# Sch_Form.net
KiCad netlist of a schematic drawn in Altium Designer
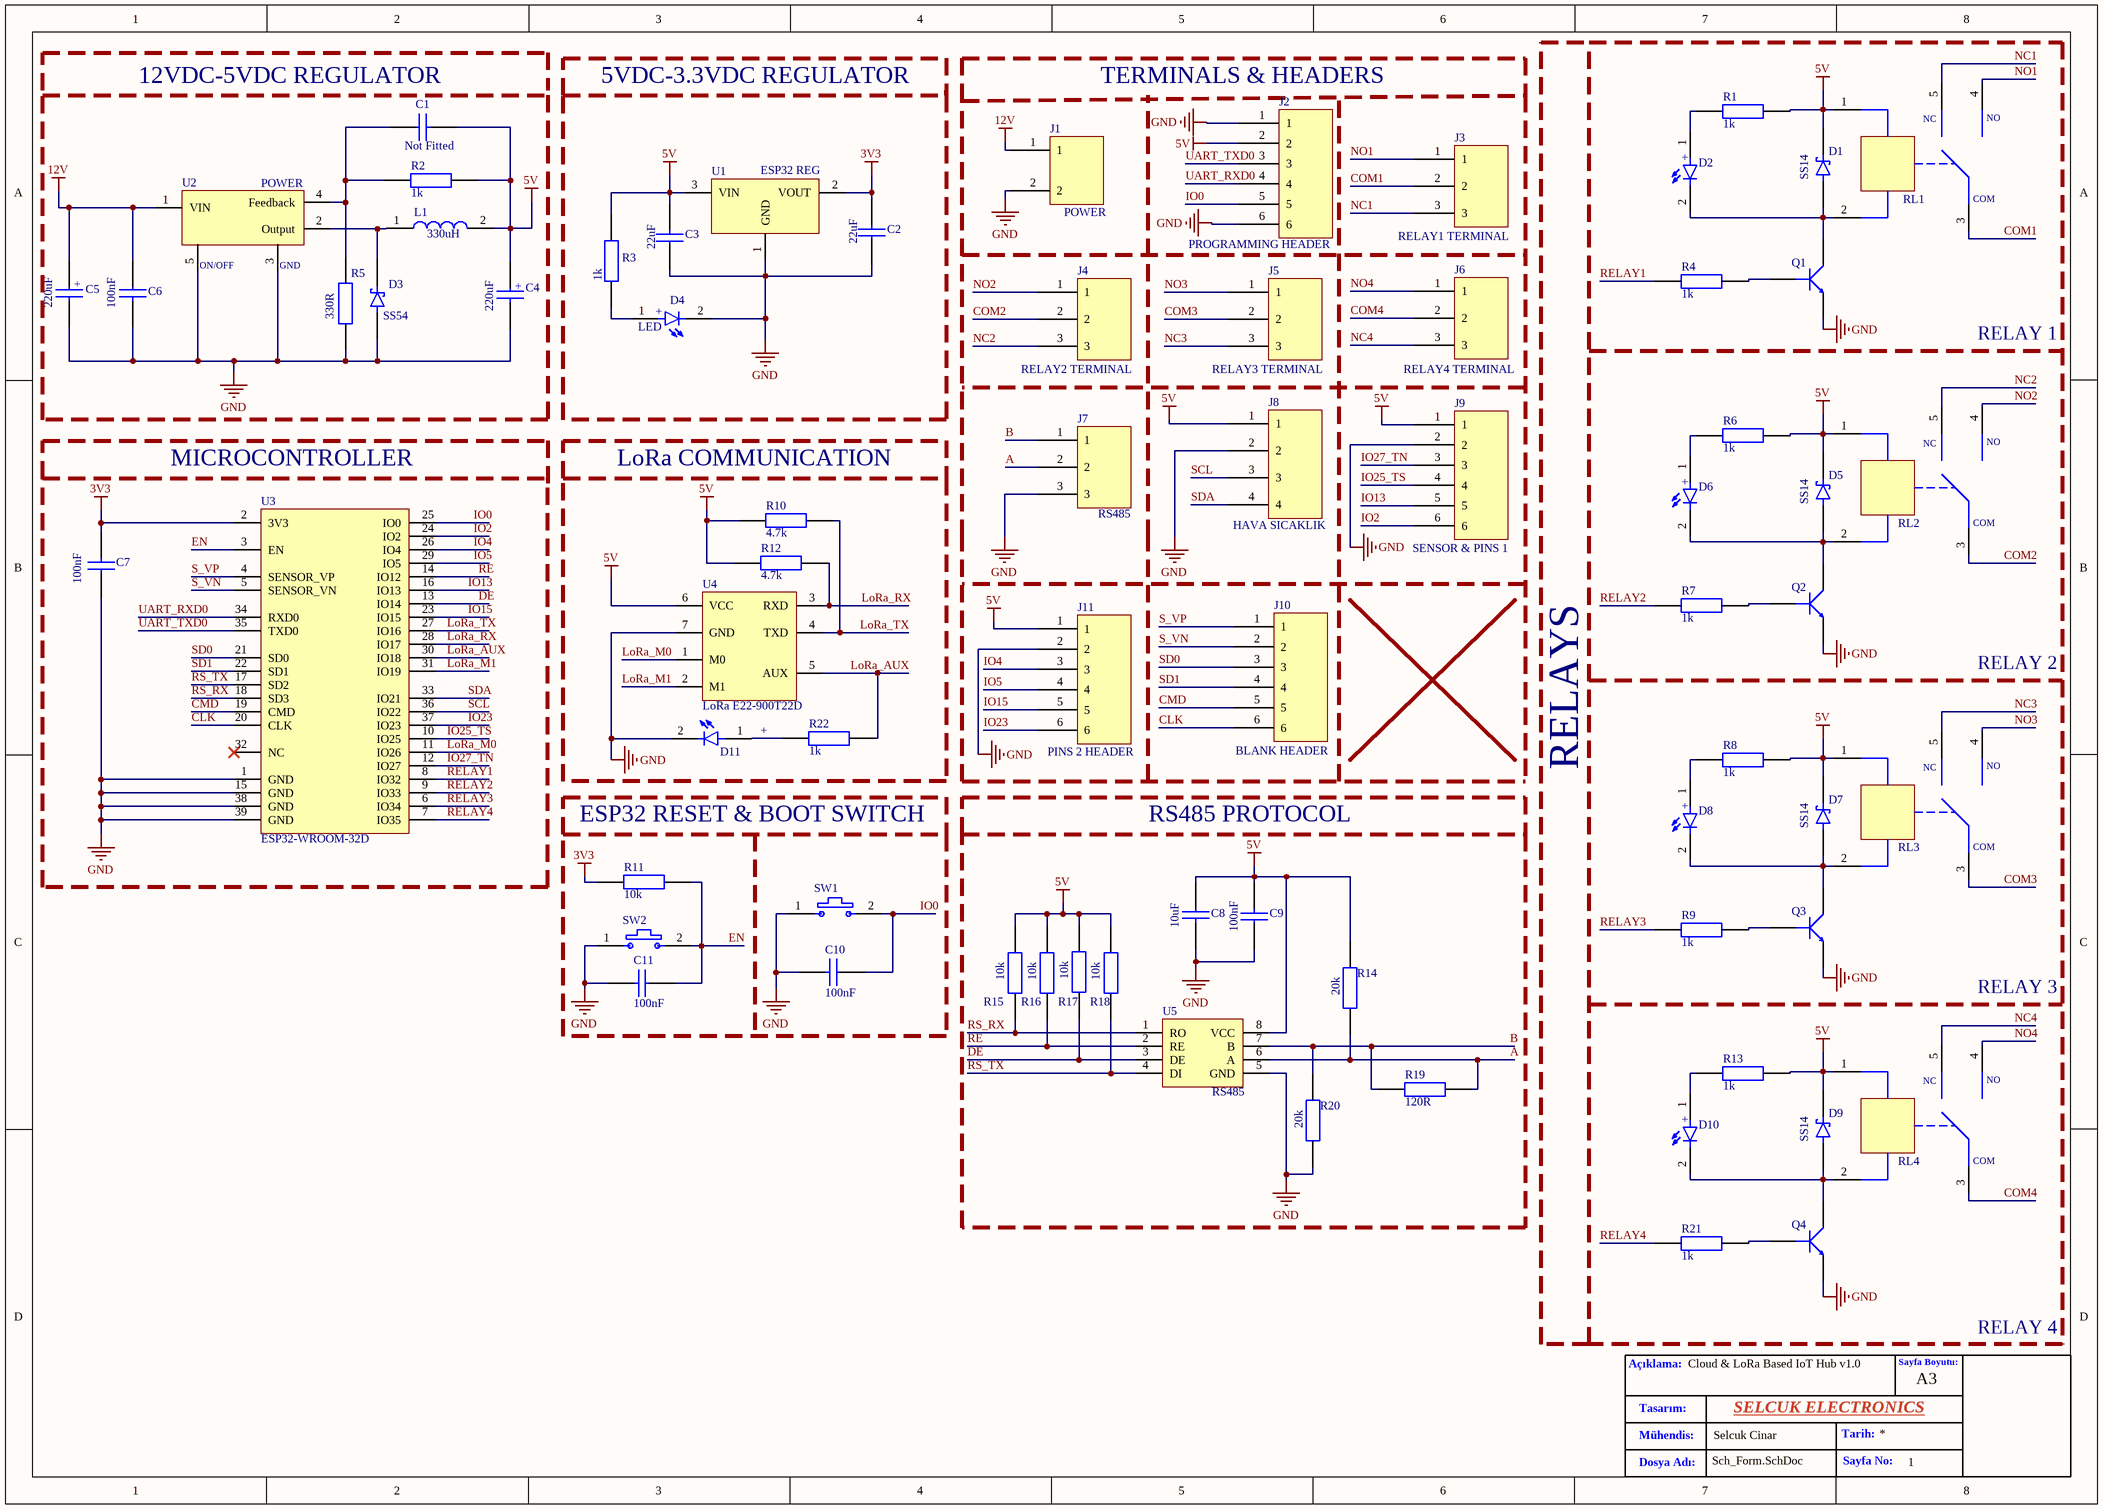
[diagram p0: Sch_Form.SchDoc]

(export (version "E")
  (design (tool "Eeschema 10.0.6"))
  (components
    (comp (ref "C1")
      (value "Not Fitted")
      (footprint "0805 FITTED CAP")
      (description "Fılter Cap(No Value) for Power Module POWER")
      (libsource (lib "Schematic_Lib") (part "FITTED 0805 CAP"))
    )
    (comp (ref "C2")
      (value "22uF")
      (footprint "0805 22uF CAP")
      (description "22uF 0805 CAP AMS1117")
      (libsource (lib "Schematic_Lib") (part "22uF 0805 CAP"))
    )
    (comp (ref "C3")
      (value "22uF")
      (footprint "0805 22uF CAP")
      (description "22uF 0805 CAP AMS1117")
      (libsource (lib "Schematic_Lib") (part "22uF 0805 CAP"))
    )
    (comp (ref "C4")
      (value "220uF")
      (footprint "220/35V/VT ECAP-0810")
      (description "Power Module 0810 Electrolyte Cap POWER")
      (libsource (lib "Schematic_Lib") (part "220/35V/VT ECAP-0810"))
    )
    (comp (ref "C5")
      (value "220uF")
      (footprint "100/50V/VT ECAP-0810")
      (description "Power Module 0810 Electrolyte Cap POWER")
      (libsource (lib "Schematic_Lib") (part "100/50V/VT ECAP-0810"))
    )
    (comp (ref "C6")
      (value "100nF")
      (footprint "0805 100nF CAP")
      (description "100nF CAP POWER")
      (libsource (lib "Schematic_Lib") (part "100nF 0805 CAP"))
    )
    (comp (ref "C7")
      (value "100nF")
      (footprint "0805 100nF CAP")
      (description "100nF CAP POWER")
      (libsource (lib "Schematic_Lib") (part "100nF 0805 CAP"))
    )
    (comp (ref "C8")
      (value "10uF")
      (footprint "1206 10uF CAP")
      (description "10uF Cap - RS485")
      (libsource (lib "Schematic_Lib") (part "10uF 1206 CAP"))
    )
    (comp (ref "C9")
      (value "100nF")
      (footprint "0805 100nF CAP")
      (description "100nF CAP POWER")
      (libsource (lib "Schematic_Lib") (part "100nF 0805 CAP"))
    )
    (comp (ref "C10")
      (value "100nF")
      (footprint "0805 100nF CAP")
      (description "100nF CAP POWER")
      (libsource (lib "Schematic_Lib") (part "100nF 0805 CAP"))
    )
    (comp (ref "C11")
      (value "100nF")
      (footprint "0805 100nF CAP")
      (description "100nF CAP POWER")
      (libsource (lib "Schematic_Lib") (part "100nF 0805 CAP"))
    )
    (comp (ref "D1")
      (value "SS14")
      (footprint "SS14-DO-214AC")
      (description "1A 40V Schottky Diode")
      (libsource (lib "Schematic_Lib") (part "SS14-DO-214AC"))
    )
    (comp (ref "D2") (value "LED") (footprint "1206 LED") (libsource (lib "Schematic_Lib") (part "1206 LED")))
    (comp (ref "D3")
      (value "SS54")
      (footprint "SS34")
      (description "SS34 SCHOTTKY DIODE MODULE POWER")
      (libsource (lib "Schematic_Lib") (part "SS34 Schottky Diode"))
    )
    (comp (ref "D4") (value "LED") (footprint "1206 LED") (libsource (lib "Schematic_Lib") (part "1206 LED")))
    (comp (ref "D5")
      (value "SS14")
      (footprint "SS14-DO-214AC")
      (description "1A 40V Schottky Diode")
      (libsource (lib "Schematic_Lib") (part "SS14-DO-214AC"))
    )
    (comp (ref "D6") (value "LED") (footprint "1206 LED") (libsource (lib "Schematic_Lib") (part "1206 LED")))
    (comp (ref "D7")
      (value "SS14")
      (footprint "SS14-DO-214AC")
      (description "1A 40V Schottky Diode")
      (libsource (lib "Schematic_Lib") (part "SS14-DO-214AC"))
    )
    (comp (ref "D8") (value "LED") (footprint "1206 LED") (libsource (lib "Schematic_Lib") (part "1206 LED")))
    (comp (ref "D9")
      (value "SS14")
      (footprint "SS14-DO-214AC")
      (description "1A 40V Schottky Diode")
      (libsource (lib "Schematic_Lib") (part "SS14-DO-214AC"))
    )
    (comp (ref "D10")
      (value "LED")
      (footprint "1206 LED")
      (libsource (lib "Schematic_Lib") (part "1206 LED"))
    )
    (comp (ref "D11")
      (value "LED")
      (footprint "1206 LED")
      (libsource (lib "Schematic_Lib") (part "1206 LED"))
    )
    (comp (ref "J1")
      (value "POWER")
      (footprint "Terminal 2")
      (description "2-PIN KLEMENS")
      (libsource (lib "Schematic_Lib") (part "TERMINAL 2"))
    )
    (comp (ref "J2")
      (value "PROGRAMMING HEADER")
      (footprint "1x6 HEADER")
      (description "1X6 HEADER")
      (libsource (lib "Schematic_Lib") (part "1x6 Header"))
    )
    (comp (ref "J3")
      (value "RELAY1 TERMINAL")
      (footprint "TERMINAL 3")
      (description "3-PIN KLEMENS")
      (libsource (lib "Schematic_Lib") (part "TERMINAL 3"))
    )
    (comp (ref "J4")
      (value "RELAY2 TERMINAL")
      (footprint "TERMINAL 3")
      (description "3-PIN KLEMENS")
      (libsource (lib "Schematic_Lib") (part "TERMINAL 3"))
    )
    (comp (ref "J5")
      (value "RELAY3 TERMINAL")
      (footprint "TERMINAL 3")
      (description "3-PIN KLEMENS")
      (libsource (lib "Schematic_Lib") (part "TERMINAL 3"))
    )
    (comp (ref "J6")
      (value "RELAY4 TERMINAL")
      (footprint "TERMINAL 3")
      (description "3-PIN KLEMENS")
      (libsource (lib "Schematic_Lib") (part "TERMINAL 3"))
    )
    (comp (ref "J7")
      (value "RS485")
      (footprint "TERMINAL 3")
      (description "3-PIN KLEMENS")
      (libsource (lib "Schematic_Lib") (part "TERMINAL 3"))
    )
    (comp (ref "J8")
      (value "HAVA SICAKLIK")
      (footprint "TERMINAL 4")
      (description "4-PIN KLEMENS")
      (libsource (lib "Schematic_Lib") (part "TERMINAL 4"))
    )
    (comp (ref "J9")
      (value "SENSOR & PINS 1")
      (footprint "TERMINAL 6")
      (description "6-PIN 90 DEGREE")
      (libsource (lib "Schematic_Lib") (part "TERMINAL 6"))
    )
    (comp (ref "J10")
      (value "BLANK HEADER")
      (footprint "1x6 HEADER")
      (description "1X6 HEADER")
      (libsource (lib "Schematic_Lib") (part "1x6 Header"))
    )
    (comp (ref "J11")
      (value "PINS 2 HEADER")
      (footprint "1x6 HEADER")
      (description "1X6 HEADER")
      (libsource (lib "Schematic_Lib") (part "1x6 Header"))
    )
    (comp (ref "L1")
      (value "POWER IND")
      (footprint "330uH/470 - INDUCTOR")
      (description "Power Module 0810 Inductor 12.3mmx12.3mm POWER")
      (libsource (lib "Schematic_Lib") (part "330uH/470 INDUCTOR"))
    )
    (comp (ref "Q1")
      (value "RELAY TRANSISTOR")
      (footprint "BC847 NPN")
      (description "BC847 Transistör Npn Smd Sot-23100mA, 45V NPN")
      (libsource (lib "Schematic_Lib") (part "BC487 TRANSISTOR"))
    )
    (comp (ref "Q2")
      (value "RELAY TRANSISTOR")
      (footprint "BC847 NPN")
      (description "BC847 Transistör Npn Smd Sot-23100mA, 45V NPN")
      (libsource (lib "Schematic_Lib") (part "BC487 TRANSISTOR"))
    )
    (comp (ref "Q3")
      (value "RELAY TRANSISTOR")
      (footprint "BC847 NPN")
      (description "BC847 Transistör Npn Smd Sot-23100mA, 45V NPN")
      (libsource (lib "Schematic_Lib") (part "BC487 TRANSISTOR"))
    )
    (comp (ref "Q4")
      (value "RELAY TRANSISTOR")
      (footprint "BC847 NPN")
      (description "BC847 Transistör Npn Smd Sot-23100mA, 45V NPN")
      (libsource (lib "Schematic_Lib") (part "BC487 TRANSISTOR"))
    )
    (comp (ref "R1")
      (value "1k")
      (footprint "0805 1K RES")
      (description "1K 0805 SMD RES POWER")
      (libsource (lib "Schematic_Lib") (part "1K 0805 RES"))
    )
    (comp (ref "R2")
      (value "1k")
      (footprint "0805 1K RES")
      (description "1K 0805 SMD RES POWER")
      (libsource (lib "Schematic_Lib") (part "1K 0805 RES"))
    )
    (comp (ref "R3")
      (value "1k")
      (footprint "0805 1K RES")
      (description "1K 0805 SMD RES POWER")
      (libsource (lib "") (part "1K 0805 RES_1"))
    )
    (comp (ref "R4")
      (value "1k")
      (footprint "0805 1K RES")
      (description "1K 0805 SMD RES POWER")
      (libsource (lib "Schematic_Lib") (part "1K 0805 RES"))
    )
    (comp (ref "R5")
      (value "330R")
      (footprint "0805 330R RES")
      (description "330R 0805 SMD RES POWER")
      (libsource (lib "Schematic_Lib") (part "330R 0805 RES"))
    )
    (comp (ref "R6")
      (value "1k")
      (footprint "0805 1K RES")
      (description "1K 0805 SMD RES POWER")
      (libsource (lib "Schematic_Lib") (part "1K 0805 RES"))
    )
    (comp (ref "R7")
      (value "1k")
      (footprint "0805 1K RES")
      (description "1K 0805 SMD RES POWER")
      (libsource (lib "Schematic_Lib") (part "1K 0805 RES"))
    )
    (comp (ref "R8")
      (value "1k")
      (footprint "0805 1K RES")
      (description "1K 0805 SMD RES POWER")
      (libsource (lib "Schematic_Lib") (part "1K 0805 RES"))
    )
    (comp (ref "R9")
      (value "1k")
      (footprint "0805 1K RES")
      (description "1K 0805 SMD RES POWER")
      (libsource (lib "Schematic_Lib") (part "1K 0805 RES"))
    )
    (comp (ref "R10")
      (value "4.7k")
      (footprint "0805 4.7k RES")
      (description "4.7k RES for LoRa Pull-Up")
      (libsource (lib "Schematic_Lib") (part "4.7k 0805 RES"))
    )
    (comp (ref "R11")
      (value "10k")
      (footprint "0805 10k RES")
      (description "10k Resistor-RS485")
      (libsource (lib "") (part "10k 0805 RES_1"))
    )
    (comp (ref "R12")
      (value "4.7k")
      (footprint "0805 4.7k RES")
      (description "4.7k RES for LoRa Pull-Up")
      (libsource (lib "Schematic_Lib") (part "4.7k 0805 RES"))
    )
    (comp (ref "R13")
      (value "1k")
      (footprint "0805 1K RES")
      (description "1K 0805 SMD RES POWER")
      (libsource (lib "Schematic_Lib") (part "1K 0805 RES"))
    )
    (comp (ref "R14")
      (value "20k")
      (footprint "0805 20k RES")
      (description "20k Resistor - RS485")
      (libsource (lib "Schematic_Lib") (part "20k 0805 RES"))
    )
    (comp (ref "R15")
      (value "10k")
      (footprint "0805 10k RES")
      (description "10k Resistor - RS485")
      (libsource (lib "Schematic_Lib") (part "10k 0805 RES"))
    )
    (comp (ref "R16")
      (value "10k")
      (footprint "0805 10k RES")
      (description "10k Resistor - RS485")
      (libsource (lib "Schematic_Lib") (part "10k 0805 RES"))
    )
    (comp (ref "R17")
      (value "10k")
      (footprint "0805 10k RES")
      (description "10k Resistor - RS485")
      (libsource (lib "Schematic_Lib") (part "10k 0805 RES"))
    )
    (comp (ref "R18")
      (value "10k")
      (footprint "0805 10k RES")
      (description "10k Resistor - RS485")
      (libsource (lib "Schematic_Lib") (part "10k 0805 RES"))
    )
    (comp (ref "R19")
      (value "120R")
      (footprint "0805 120R RES")
      (description "120R Resistor - RS485")
      (libsource (lib "Schematic_Lib") (part "120R 0805 RES"))
    )
    (comp (ref "R20")
      (value "20k")
      (footprint "0805 20k RES")
      (description "20k Resistor - RS485")
      (libsource (lib "Schematic_Lib") (part "20k 0805 RES"))
    )
    (comp (ref "R21")
      (value "1k")
      (footprint "0805 1K RES")
      (description "1K 0805 SMD RES POWER")
      (libsource (lib "Schematic_Lib") (part "1K 0805 RES"))
    )
    (comp (ref "R22")
      (value "1k")
      (footprint "0805 1K RES")
      (description "1K 0805 SMD RES POWER")
      (libsource (lib "Schematic_Lib") (part "1K 0805 RES"))
    )
    (comp (ref "RL1")
      (value "3V3 RELAY")
      (footprint "SONGLE SRD-03VDC-SL-C")
      (description "3.3V Relay")
      (libsource (lib "Schematic_Lib") (part "SRD-03VDC-SL-C"))
    )
    (comp (ref "RL2")
      (value "3V3 RELAY")
      (footprint "SONGLE SRD-03VDC-SL-C")
      (description "3.3V Relay")
      (libsource (lib "Schematic_Lib") (part "SRD-03VDC-SL-C"))
    )
    (comp (ref "RL3")
      (value "3V3 RELAY")
      (footprint "SONGLE SRD-03VDC-SL-C")
      (description "3.3V Relay")
      (libsource (lib "Schematic_Lib") (part "SRD-03VDC-SL-C"))
    )
    (comp (ref "RL4")
      (value "3V3 RELAY")
      (footprint "SONGLE SRD-03VDC-SL-C")
      (description "3.3V Relay")
      (libsource (lib "Schematic_Lib") (part "SRD-03VDC-SL-C"))
    )
    (comp (ref "SW1")
      (value "SWITCH")
      (footprint "BUTTON")
      (description "Switch For ESP32")
      (libsource (lib "Schematic_Lib") (part "BUTTON"))
    )
    (comp (ref "SW2")
      (value "SWITCH")
      (footprint "BUTTON")
      (description "Switch For ESP32")
      (libsource (lib "Schematic_Lib") (part "BUTTON"))
    )
    (comp (ref "U1")
      (value "ESP32 REG")
      (footprint "AMS1117")
      (description "5V to 3V3 Reg. for ESP32")
      (libsource (lib "Schematic_Lib") (part "AMS1117-3.3V REG"))
    )
    (comp (ref "U2")
      (value "POWER")
      (footprint "LM2596S")
      (description "5V REGULATOR")
      (libsource (lib "Schematic_Lib") (part "LM2596S"))
    )
    (comp (ref "U3")
      (value "ESP32-WROOM-32D")
      (footprint "ESP32-WROOM-32D")
      (description "SMD MODULE, ESP32-D0WDQ6, 32MBIT (FootPrint ölçüleri doğru 3D 'ye takılma)")
      (libsource (lib "Schematic_Lib") (part "ESP32-WROOM-32D"))
    )
    (comp (ref "U4")
      (value "LoRa E22-900T22D")
      (footprint "E22-900T22D")
      (description "Ebyte LoRa 22dBm 5-7km Communication Module")
      (libsource (lib "Schematic_Lib") (part "E22-900T22D"))
    )
    (comp (ref "U5")
      (value "RS485")
      (footprint "MAX485")
      (description "RS485 Chip")
      (libsource (lib "Schematic_Lib") (part "MAX485"))
    )
  )
  (nets
    (net (code "1") (name "/A") (class "Default")
      (node (ref "J7") (pin "2") (pinfunction "2_2") (pintype "passive"))
      (node (ref "R14") (pin "1") (pinfunction "1_1") (pintype "passive"))
      (node (ref "R19") (pin "2") (pinfunction "2_2") (pintype "passive"))
      (node (ref "U5") (pin "6") (pinfunction "A_6") (pintype "passive"))
    )
    (net (code "2") (name "/B") (class "Default")
      (node (ref "J7") (pin "1") (pinfunction "1_1") (pintype "passive"))
      (node (ref "R19") (pin "1") (pinfunction "1_1") (pintype "passive"))
      (node (ref "R20") (pin "2") (pinfunction "2_2") (pintype "passive"))
      (node (ref "U5") (pin "7") (pinfunction "B_7") (pintype "passive"))
    )
    (net (code "3") (name "/CLK") (class "Default")
      (node (ref "J10") (pin "6") (pinfunction "6_6") (pintype "passive"))
      (node (ref "U3") (pin "20") (pinfunction "CLK_20") (pintype "passive"))
    )
    (net (code "4") (name "/CMD") (class "Default")
      (node (ref "J10") (pin "5") (pinfunction "5_5") (pintype "passive"))
      (node (ref "U3") (pin "19") (pinfunction "CMD_19") (pintype "passive"))
    )
    (net (code "5") (name "/COM1") (class "Default")
      (node (ref "J3") (pin "2") (pinfunction "2_2") (pintype "passive"))
      (node (ref "RL1") (pin "3") (pinfunction "COM_3") (pintype "passive"))
    )
    (net (code "6") (name "/COM2") (class "Default")
      (node (ref "J4") (pin "2") (pinfunction "2_2") (pintype "passive"))
      (node (ref "RL2") (pin "3") (pinfunction "COM_3") (pintype "passive"))
    )
    (net (code "7") (name "/COM3") (class "Default")
      (node (ref "J5") (pin "2") (pinfunction "2_2") (pintype "passive"))
      (node (ref "RL3") (pin "3") (pinfunction "COM_3") (pintype "passive"))
    )
    (net (code "8") (name "/COM4") (class "Default")
      (node (ref "J6") (pin "2") (pinfunction "2_2") (pintype "passive"))
      (node (ref "RL4") (pin "3") (pinfunction "COM_3") (pintype "passive"))
    )
    (net (code "9") (name "/DE") (class "Default")
      (node (ref "R17") (pin "1") (pinfunction "1_1") (pintype "passive"))
      (node (ref "U3") (pin "13") (pinfunction "IO14_13") (pintype "passive"))
      (node (ref "U5") (pin "3") (pinfunction "DE_3") (pintype "passive"))
    )
    (net (code "10") (name "/EN") (class "Default")
      (node (ref "C11") (pin "2") (pinfunction "2_2") (pintype "passive"))
      (node (ref "R11") (pin "2") (pinfunction "2_2") (pintype "passive"))
      (node (ref "SW2") (pin "2") (pinfunction "2_2") (pintype "passive"))
      (node (ref "U3") (pin "3") (pinfunction "EN_3") (pintype "passive"))
    )
    (net (code "11") (name "/IO0") (class "Default")
      (node (ref "C10") (pin "2") (pinfunction "2_2") (pintype "passive"))
      (node (ref "J2") (pin "5") (pinfunction "5_5") (pintype "passive"))
      (node (ref "SW1") (pin "2") (pinfunction "2_2") (pintype "passive"))
      (node (ref "U3") (pin "25") (pinfunction "IO0_25") (pintype "passive"))
    )
    (net (code "12") (name "/IO2") (class "Default")
      (node (ref "J9") (pin "6") (pinfunction "6_6") (pintype "passive"))
      (node (ref "U3") (pin "24") (pinfunction "IO2_24") (pintype "passive"))
    )
    (net (code "13") (name "/IO4") (class "Default")
      (node (ref "J11") (pin "3") (pinfunction "3_3") (pintype "passive"))
      (node (ref "U3") (pin "26") (pinfunction "IO4_26") (pintype "passive"))
    )
    (net (code "14") (name "/IO5") (class "Default")
      (node (ref "J11") (pin "4") (pinfunction "4_4") (pintype "passive"))
      (node (ref "U3") (pin "29") (pinfunction "IO5_29") (pintype "passive"))
    )
    (net (code "15") (name "/IO13") (class "Default")
      (node (ref "J9") (pin "5") (pinfunction "5_5") (pintype "passive"))
      (node (ref "U3") (pin "16") (pinfunction "IO13_16") (pintype "passive"))
    )
    (net (code "16") (name "/IO15") (class "Default")
      (node (ref "J11") (pin "5") (pinfunction "5_5") (pintype "passive"))
      (node (ref "U3") (pin "23") (pinfunction "IO15_23") (pintype "passive"))
    )
    (net (code "17") (name "/IO23") (class "Default")
      (node (ref "J11") (pin "6") (pinfunction "6_6") (pintype "passive"))
      (node (ref "U3") (pin "37") (pinfunction "IO23_37") (pintype "passive"))
    )
    (net (code "18") (name "/IO25_TS") (class "Default")
      (node (ref "J9") (pin "4") (pinfunction "4_4") (pintype "passive"))
      (node (ref "U3") (pin "10") (pinfunction "IO25_10") (pintype "passive"))
    )
    (net (code "19") (name "/IO27_TN") (class "Default")
      (node (ref "J9") (pin "3") (pinfunction "3_3") (pintype "passive"))
      (node (ref "U3") (pin "12") (pinfunction "IO27_12") (pintype "passive"))
    )
    (net (code "20") (name "/LoRa_AUX") (class "Default")
      (node (ref "R22") (pin "2") (pinfunction "2_2") (pintype "passive"))
      (node (ref "U3") (pin "30") (pinfunction "IO18_30") (pintype "passive"))
      (node (ref "U4") (pin "5") (pinfunction "AUX_5") (pintype "passive"))
    )
    (net (code "21") (name "/LoRa_M0") (class "Default")
      (node (ref "U3") (pin "11") (pinfunction "IO26_11") (pintype "passive"))
      (node (ref "U4") (pin "1") (pinfunction "M0_1") (pintype "passive"))
    )
    (net (code "22") (name "/LoRa_M1") (class "Default")
      (node (ref "U3") (pin "31") (pinfunction "IO19_31") (pintype "passive"))
      (node (ref "U4") (pin "2") (pinfunction "M1_2") (pintype "passive"))
    )
    (net (code "23") (name "/LoRa_RX") (class "Default")
      (node (ref "R12") (pin "1") (pinfunction "1_1") (pintype "passive"))
      (node (ref "U3") (pin "28") (pinfunction "IO17_28") (pintype "passive"))
      (node (ref "U4") (pin "3") (pinfunction "RXD_3") (pintype "passive"))
    )
    (net (code "24") (name "/LoRa_TX") (class "Default")
      (node (ref "R10") (pin "1") (pinfunction "1_1") (pintype "passive"))
      (node (ref "U3") (pin "27") (pinfunction "IO16_27") (pintype "passive"))
      (node (ref "U4") (pin "4") (pinfunction "TXD_4") (pintype "passive"))
    )
    (net (code "25") (name "/NC1") (class "Default")
      (node (ref "J3") (pin "3") (pinfunction "3_3") (pintype "passive"))
      (node (ref "RL1") (pin "5") (pinfunction "NC_5") (pintype "passive"))
    )
    (net (code "26") (name "/NC2") (class "Default")
      (node (ref "J4") (pin "3") (pinfunction "3_3") (pintype "passive"))
      (node (ref "RL2") (pin "5") (pinfunction "NC_5") (pintype "passive"))
    )
    (net (code "27") (name "/NC3") (class "Default")
      (node (ref "J5") (pin "3") (pinfunction "3_3") (pintype "passive"))
      (node (ref "RL3") (pin "5") (pinfunction "NC_5") (pintype "passive"))
    )
    (net (code "28") (name "/NC4") (class "Default")
      (node (ref "J6") (pin "3") (pinfunction "3_3") (pintype "passive"))
      (node (ref "RL4") (pin "5") (pinfunction "NC_5") (pintype "passive"))
    )
    (net (code "29") (name "/NO1") (class "Default")
      (node (ref "J3") (pin "1") (pinfunction "1_1") (pintype "passive"))
      (node (ref "RL1") (pin "4") (pinfunction "NO_4") (pintype "passive"))
    )
    (net (code "30") (name "/NO2") (class "Default")
      (node (ref "J4") (pin "1") (pinfunction "1_1") (pintype "passive"))
      (node (ref "RL2") (pin "4") (pinfunction "NO_4") (pintype "passive"))
    )
    (net (code "31") (name "/NO3") (class "Default")
      (node (ref "J5") (pin "1") (pinfunction "1_1") (pintype "passive"))
      (node (ref "RL3") (pin "4") (pinfunction "NO_4") (pintype "passive"))
    )
    (net (code "32") (name "/NO4") (class "Default")
      (node (ref "J6") (pin "1") (pinfunction "1_1") (pintype "passive"))
      (node (ref "RL4") (pin "4") (pinfunction "NO_4") (pintype "passive"))
    )
    (net (code "33") (name "/RE") (class "Default")
      (node (ref "R16") (pin "1") (pinfunction "1_1") (pintype "passive"))
      (node (ref "U3") (pin "14") (pinfunction "IO12_14") (pintype "passive"))
      (node (ref "U5") (pin "2") (pinfunction "RE_2") (pintype "passive"))
    )
    (net (code "34") (name "/RELAY1") (class "Default")
      (node (ref "R4") (pin "1") (pinfunction "1_1") (pintype "passive"))
      (node (ref "U3") (pin "8") (pinfunction "IO32_8") (pintype "passive"))
    )
    (net (code "35") (name "/RELAY2") (class "Default")
      (node (ref "R7") (pin "1") (pinfunction "1_1") (pintype "passive"))
      (node (ref "U3") (pin "9") (pinfunction "IO33_9") (pintype "passive"))
    )
    (net (code "36") (name "/RELAY3") (class "Default")
      (node (ref "R9") (pin "1") (pinfunction "1_1") (pintype "passive"))
      (node (ref "U3") (pin "6") (pinfunction "IO34_6") (pintype "passive"))
    )
    (net (code "37") (name "/RELAY4") (class "Default")
      (node (ref "R21") (pin "1") (pinfunction "1_1") (pintype "passive"))
      (node (ref "U3") (pin "7") (pinfunction "IO35_7") (pintype "passive"))
    )
    (net (code "38") (name "/RS_RX") (class "Default")
      (node (ref "R15") (pin "1") (pinfunction "1_1") (pintype "passive"))
      (node (ref "U3") (pin "18") (pinfunction "SD3_18") (pintype "passive"))
      (node (ref "U5") (pin "1") (pinfunction "RO_1") (pintype "passive"))
    )
    (net (code "39") (name "/RS_TX") (class "Default")
      (node (ref "R18") (pin "1") (pinfunction "1_1") (pintype "passive"))
      (node (ref "U3") (pin "17") (pinfunction "SD2_17") (pintype "passive"))
      (node (ref "U5") (pin "4") (pinfunction "DI_4") (pintype "passive"))
    )
    (net (code "40") (name "/SCL") (class "Default")
      (node (ref "J8") (pin "3") (pinfunction "3_3") (pintype "passive"))
      (node (ref "U3") (pin "36") (pinfunction "IO22_36") (pintype "passive"))
    )
    (net (code "41") (name "/SD0") (class "Default")
      (node (ref "J10") (pin "3") (pinfunction "3_3") (pintype "passive"))
      (node (ref "U3") (pin "21") (pinfunction "SD0_21") (pintype "passive"))
    )
    (net (code "42") (name "/SD1") (class "Default")
      (node (ref "J10") (pin "4") (pinfunction "4_4") (pintype "passive"))
      (node (ref "U3") (pin "22") (pinfunction "SD1_22") (pintype "passive"))
    )
    (net (code "43") (name "/SDA") (class "Default")
      (node (ref "J8") (pin "4") (pinfunction "4_4") (pintype "passive"))
      (node (ref "U3") (pin "33") (pinfunction "IO21_33") (pintype "passive"))
    )
    (net (code "44") (name "/S_VN") (class "Default")
      (node (ref "J10") (pin "2") (pinfunction "2_2") (pintype "passive"))
      (node (ref "U3") (pin "5") (pinfunction "SENSOR_VN_5") (pintype "passive"))
    )
    (net (code "45") (name "/S_VP") (class "Default")
      (node (ref "J10") (pin "1") (pinfunction "1_1") (pintype "passive"))
      (node (ref "U3") (pin "4") (pinfunction "SENSOR_VP_4") (pintype "passive"))
    )
    (net (code "46") (name "/UART_RXD0") (class "Default")
      (node (ref "J2") (pin "4") (pinfunction "4_4") (pintype "passive"))
      (node (ref "U3") (pin "34") (pinfunction "RXD0_34") (pintype "passive"))
    )
    (net (code "47") (name "/UART_TXD0") (class "Default")
      (node (ref "J2") (pin "3") (pinfunction "3_3") (pintype "passive"))
      (node (ref "U3") (pin "35") (pinfunction "TXD0_35") (pintype "passive"))
    )
    (net (code "48") (name "3V3") (class "Default")
      (node (ref "C2") (pin "1") (pinfunction "1_1") (pintype "passive"))
      (node (ref "C7") (pin "1") (pinfunction "1_1") (pintype "passive"))
      (node (ref "R11") (pin "1") (pinfunction "1_1") (pintype "passive"))
      (node (ref "U1") (pin "2") (pinfunction "VOUT_2") (pintype "passive"))
      (node (ref "U3") (pin "2") (pinfunction "3V3_2") (pintype "passive"))
    )
    (net (code "49") (name "5V") (class "Default")
      (node (ref "C1") (pin "1") (pinfunction "1_1") (pintype "passive"))
      (node (ref "C3") (pin "1") (pinfunction "1_1") (pintype "passive"))
      (node (ref "C4") (pin "1") (pinfunction "+_1") (pintype "passive"))
      (node (ref "C8") (pin "2") (pinfunction "2_2") (pintype "passive"))
      (node (ref "C9") (pin "1") (pinfunction "1_1") (pintype "passive"))
      (node (ref "D1") (pin "2") (pinfunction "2_2") (pintype "passive"))
      (node (ref "D5") (pin "2") (pinfunction "2_2") (pintype "passive"))
      (node (ref "D7") (pin "2") (pinfunction "2_2") (pintype "passive"))
      (node (ref "D9") (pin "2") (pinfunction "2_2") (pintype "passive"))
      (node (ref "J11") (pin "1") (pinfunction "1_1") (pintype "passive"))
      (node (ref "J2") (pin "2") (pinfunction "2_2") (pintype "passive"))
      (node (ref "J8") (pin "1") (pinfunction "1_1") (pintype "passive"))
      (node (ref "J9") (pin "1") (pinfunction "1_1") (pintype "passive"))
      (node (ref "L1") (pin "2") (pinfunction "2_2") (pintype "passive"))
      (node (ref "R1") (pin "2") (pinfunction "2_2") (pintype "passive"))
      (node (ref "R10") (pin "2") (pinfunction "2_2") (pintype "passive"))
      (node (ref "R12") (pin "2") (pinfunction "2_2") (pintype "passive"))
      (node (ref "R13") (pin "2") (pinfunction "2_2") (pintype "passive"))
      (node (ref "R14") (pin "2") (pinfunction "2_2") (pintype "passive"))
      (node (ref "R15") (pin "2") (pinfunction "2_2") (pintype "passive"))
      (node (ref "R16") (pin "2") (pinfunction "2_2") (pintype "passive"))
      (node (ref "R17") (pin "2") (pinfunction "2_2") (pintype "passive"))
      (node (ref "R18") (pin "2") (pinfunction "2_2") (pintype "passive"))
      (node (ref "R2") (pin "2") (pinfunction "2_2") (pintype "passive"))
      (node (ref "R3") (pin "2") (pinfunction "2_2") (pintype "passive"))
      (node (ref "R6") (pin "2") (pinfunction "2_2") (pintype "passive"))
      (node (ref "R8") (pin "2") (pinfunction "2_2") (pintype "passive"))
      (node (ref "RL1") (pin "1") (pinfunction "+_1") (pintype "passive"))
      (node (ref "RL2") (pin "1") (pinfunction "+_1") (pintype "passive"))
      (node (ref "RL3") (pin "1") (pinfunction "+_1") (pintype "passive"))
      (node (ref "RL4") (pin "1") (pinfunction "+_1") (pintype "passive"))
      (node (ref "U1") (pin "3") (pinfunction "VIN_3") (pintype "passive"))
      (node (ref "U4") (pin "6") (pinfunction "VCC_6") (pintype "passive"))
      (node (ref "U5") (pin "8") (pinfunction "VCC_8") (pintype "passive"))
    )
    (net (code "50") (name "12V") (class "Default")
      (node (ref "C5") (pin "1") (pinfunction "+_1") (pintype "passive"))
      (node (ref "C6") (pin "2") (pinfunction "2_2") (pintype "passive"))
      (node (ref "J1") (pin "1") (pinfunction "1_1") (pintype "passive"))
      (node (ref "U2") (pin "1") (pinfunction "VIN_1") (pintype "passive"))
    )
    (net (code "51") (name "GND") (class "Default")
      (node (ref "C10") (pin "1") (pinfunction "1_1") (pintype "passive"))
      (node (ref "C11") (pin "1") (pinfunction "1_1") (pintype "passive"))
      (node (ref "C2") (pin "2") (pinfunction "2_2") (pintype "passive"))
      (node (ref "C3") (pin "2") (pinfunction "2_2") (pintype "passive"))
      (node (ref "C4") (pin "2") (pinfunction "-_2") (pintype "passive"))
      (node (ref "C5") (pin "2") (pinfunction "-_2") (pintype "passive"))
      (node (ref "C6") (pin "1") (pinfunction "1_1") (pintype "passive"))
      (node (ref "C7") (pin "2") (pinfunction "2_2") (pintype "passive"))
      (node (ref "C8") (pin "1") (pinfunction "1_1") (pintype "passive"))
      (node (ref "C9") (pin "2") (pinfunction "2_2") (pintype "passive"))
      (node (ref "D11") (pin "2") (pinfunction "2_2") (pintype "passive"))
      (node (ref "D3") (pin "1") (pinfunction "A_1") (pintype "passive"))
      (node (ref "D4") (pin "2") (pinfunction "2_2") (pintype "passive"))
      (node (ref "J1") (pin "2") (pinfunction "2_2") (pintype "passive"))
      (node (ref "J11") (pin "2") (pinfunction "2_2") (pintype "passive"))
      (node (ref "J2") (pin "1") (pinfunction "1_1") (pintype "passive"))
      (node (ref "J2") (pin "6") (pinfunction "6_6") (pintype "passive"))
      (node (ref "J7") (pin "3") (pinfunction "3_3") (pintype "passive"))
      (node (ref "J8") (pin "2") (pinfunction "2_2") (pintype "passive"))
      (node (ref "J9") (pin "2") (pinfunction "2_2") (pintype "passive"))
      (node (ref "Q1") (pin "2") (pinfunction "E_2") (pintype "power_in"))
      (node (ref "Q2") (pin "2") (pinfunction "E_2") (pintype "power_in"))
      (node (ref "Q3") (pin "2") (pinfunction "E_2") (pintype "power_in"))
      (node (ref "Q4") (pin "2") (pinfunction "E_2") (pintype "power_in"))
      (node (ref "R20") (pin "1") (pinfunction "1_1") (pintype "passive"))
      (node (ref "R5") (pin "1") (pinfunction "1_1") (pintype "passive"))
      (node (ref "SW1") (pin "1") (pinfunction "1_1") (pintype "passive"))
      (node (ref "SW2") (pin "1") (pinfunction "1_1") (pintype "passive"))
      (node (ref "U1") (pin "1") (pinfunction "GND_1") (pintype "passive"))
      (node (ref "U2") (pin "3") (pinfunction "GND_3") (pintype "passive"))
      (node (ref "U2") (pin "5") (pinfunction "ON/OFF_5") (pintype "passive"))
      (node (ref "U3") (pin "1") (pinfunction "GND_1") (pintype "passive"))
      (node (ref "U3") (pin "15") (pinfunction "GND_15") (pintype "passive"))
      (node (ref "U3") (pin "38") (pinfunction "GND_38") (pintype "passive"))
      (node (ref "U3") (pin "39") (pinfunction "GND_39") (pintype "passive"))
      (node (ref "U4") (pin "7") (pinfunction "GND_7") (pintype "passive"))
      (node (ref "U5") (pin "5") (pinfunction "GND_5") (pintype "passive"))
    )
    (net (code "52") (name "Net-(D2-Pad1)") (class "Default")
      (node (ref "D2") (pin "1") (pinfunction "1_1") (pintype "passive"))
      (node (ref "R1") (pin "1") (pinfunction "1_1") (pintype "passive"))
    )
    (net (code "53") (name "Net-(D3-K)") (class "Default")
      (node (ref "D3") (pin "2") (pinfunction "K_2") (pintype "passive"))
      (node (ref "L1") (pin "1") (pinfunction "1_1") (pintype "passive"))
      (node (ref "U2") (pin "2") (pinfunction "Output_2") (pintype "passive"))
    )
    (net (code "54") (name "Net-(D4-Pad1)") (class "Default")
      (node (ref "D4") (pin "1") (pinfunction "1_1") (pintype "passive"))
      (node (ref "R3") (pin "1") (pinfunction "1_1") (pintype "passive"))
    )
    (net (code "55") (name "Net-(D6-Pad1)") (class "Default")
      (node (ref "D6") (pin "1") (pinfunction "1_1") (pintype "passive"))
      (node (ref "R6") (pin "1") (pinfunction "1_1") (pintype "passive"))
    )
    (net (code "56") (name "Net-(D8-Pad1)") (class "Default")
      (node (ref "D8") (pin "1") (pinfunction "1_1") (pintype "passive"))
      (node (ref "R8") (pin "1") (pinfunction "1_1") (pintype "passive"))
    )
    (net (code "57") (name "Net-(D10-Pad1)") (class "Default")
      (node (ref "D10") (pin "1") (pinfunction "1_1") (pintype "passive"))
      (node (ref "R13") (pin "1") (pinfunction "1_1") (pintype "passive"))
    )
    (net (code "58") (name "Net-(D11-Pad1)") (class "Default")
      (node (ref "D11") (pin "1") (pinfunction "1_1") (pintype "passive"))
      (node (ref "R22") (pin "1") (pinfunction "1_1") (pintype "passive"))
    )
    (net (code "59") (name "Net-(Q1-B)") (class "Default")
      (node (ref "Q1") (pin "1") (pinfunction "B_1") (pintype "power_in"))
      (node (ref "R4") (pin "2") (pinfunction "2_2") (pintype "passive"))
    )
    (net (code "60") (name "Net-(Q1-C)") (class "Default")
      (node (ref "D1") (pin "1") (pinfunction "1_1") (pintype "passive"))
      (node (ref "D2") (pin "2") (pinfunction "2_2") (pintype "passive"))
      (node (ref "Q1") (pin "3") (pinfunction "C_3") (pintype "power_in"))
      (node (ref "RL1") (pin "2") (pinfunction "-_2") (pintype "passive"))
    )
    (net (code "61") (name "Net-(Q2-B)") (class "Default")
      (node (ref "Q2") (pin "1") (pinfunction "B_1") (pintype "power_in"))
      (node (ref "R7") (pin "2") (pinfunction "2_2") (pintype "passive"))
    )
    (net (code "62") (name "Net-(Q2-C)") (class "Default")
      (node (ref "D5") (pin "1") (pinfunction "1_1") (pintype "passive"))
      (node (ref "D6") (pin "2") (pinfunction "2_2") (pintype "passive"))
      (node (ref "Q2") (pin "3") (pinfunction "C_3") (pintype "power_in"))
      (node (ref "RL2") (pin "2") (pinfunction "-_2") (pintype "passive"))
    )
    (net (code "63") (name "Net-(Q3-B)") (class "Default")
      (node (ref "Q3") (pin "1") (pinfunction "B_1") (pintype "power_in"))
      (node (ref "R9") (pin "2") (pinfunction "2_2") (pintype "passive"))
    )
    (net (code "64") (name "Net-(Q3-C)") (class "Default")
      (node (ref "D7") (pin "1") (pinfunction "1_1") (pintype "passive"))
      (node (ref "D8") (pin "2") (pinfunction "2_2") (pintype "passive"))
      (node (ref "Q3") (pin "3") (pinfunction "C_3") (pintype "power_in"))
      (node (ref "RL3") (pin "2") (pinfunction "-_2") (pintype "passive"))
    )
    (net (code "65") (name "Net-(Q4-B)") (class "Default")
      (node (ref "Q4") (pin "1") (pinfunction "B_1") (pintype "power_in"))
      (node (ref "R21") (pin "2") (pinfunction "2_2") (pintype "passive"))
    )
    (net (code "66") (name "Net-(Q4-C)") (class "Default")
      (node (ref "D10") (pin "2") (pinfunction "2_2") (pintype "passive"))
      (node (ref "D9") (pin "1") (pinfunction "1_1") (pintype "passive"))
      (node (ref "Q4") (pin "3") (pinfunction "C_3") (pintype "power_in"))
      (node (ref "RL4") (pin "2") (pinfunction "-_2") (pintype "passive"))
    )
    (net (code "67") (name "Net-(U2-Feedback)") (class "Default")
      (node (ref "C1") (pin "2") (pinfunction "2_2") (pintype "passive"))
      (node (ref "R2") (pin "1") (pinfunction "1_1") (pintype "passive"))
      (node (ref "R5") (pin "2") (pinfunction "2_2") (pintype "passive"))
      (node (ref "U2") (pin "4") (pinfunction "Feedback_4") (pintype "passive"))
    )
    (net (code "68") (name "unconnected-(U3-NC-Pad32)") (class "Default")
      (node (ref "U3") (pin "32") (pinfunction "NC_32") (pintype "passive+no_connect"))
    )
  )
)
